# USB.net
KiCad netlist of a schematic drawn in Altium Designer
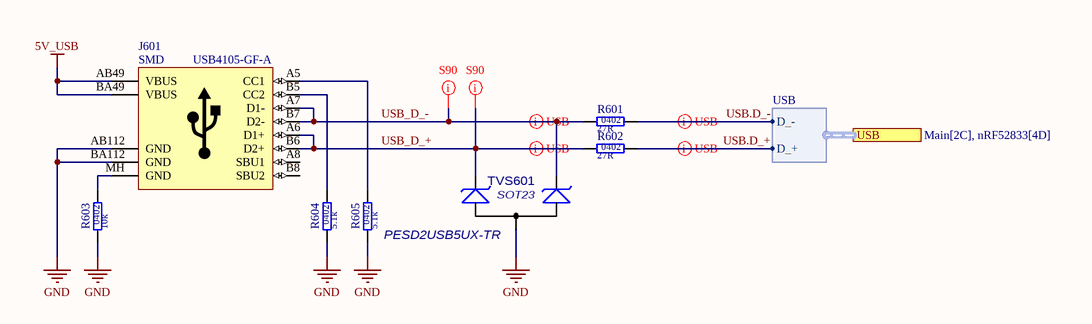
[diagram p0: USB.SchDoc]

(export (version "E")
  (design (tool "Eeschema 10.0.6"))
  (components
    (comp (ref "J601")
      (value "USB4105-GF-A")
      (footprint "J_USB_C_USB4105")
      (fields
        (field (name "SCH_FOOTPRINT") "SMD")
        (field (name "PART NUMBER") "J_USB_C_USB4105-GF-A")
        (field (name "MANUFACTURER") "GCT")
        (field (name "Comment") "USB C Connector")
      )
      (libsource (lib "Library") (part "J_USB_C_2.0_USB4105"))
    )
    (comp (ref "R601")
      (value "27R")
      (footprint "R_0402_1005")
      (fields
        (field (name "SCH_FOOTPRINT") "0402")
        (field (name "PART NUMBER") "R_27R_0402_1")
        (field (name "VOLTAGE") "50V")
        (field (name "POWER") "63mW")
      )
      (libsource (lib "Library") (part "R"))
    )
    (comp (ref "R602")
      (value "27R")
      (footprint "R_0402_1005")
      (fields
        (field (name "SCH_FOOTPRINT") "0402")
        (field (name "PART NUMBER") "R_27R_0402_1")
        (field (name "VOLTAGE") "50V")
        (field (name "POWER") "63mW")
      )
      (libsource (lib "Library") (part "R"))
    )
    (comp (ref "R603")
      (value "10k")
      (footprint "R_0402_1005")
      (fields
        (field (name "SCH_FOOTPRINT") "0402")
        (field (name "PART NUMBER") "R_10k_0402_1")
        (field (name "VOLTAGE") "50V")
        (field (name "POWER") "63mW")
      )
      (libsource (lib "Library") (part "R"))
    )
    (comp (ref "R604")
      (value "5.1k")
      (footprint "R_0402_1005")
      (fields
        (field (name "SCH_FOOTPRINT") "0402")
        (field (name "PART NUMBER") "R_5.1k_0402_1")
        (field (name "VOLTAGE") "50V")
        (field (name "POWER") "63mW")
      )
      (libsource (lib "Library") (part "R"))
    )
    (comp (ref "R605")
      (value "5.1k")
      (footprint "R_0402_1005")
      (fields
        (field (name "SCH_FOOTPRINT") "0402")
        (field (name "PART NUMBER") "R_5.1k_0402_1")
        (field (name "VOLTAGE") "50V")
        (field (name "POWER") "63mW")
      )
      (libsource (lib "Library") (part "R"))
    )
    (comp (ref "TVS601")
      (value "PESD2USB5UX-TR")
      (footprint "SOT23_N")
      (fields
        (field (name "SCH_FOOTPRINT") "SOT23")
        (field (name "PART NUMBER") "TVS_PESD2USB5UX-TR")
        (field (name "VOLTAGE") "5.0V")
        (field (name "MANUFACTURER") "Nexperia")
      )
      (libsource (lib "Library") (part "TVS_DOUBLE_SOT23-3"))
    )
  )
  (nets
    (net (code "2") (name "/USB.D_+") (class "Default")
      (node (ref "R602") (pin "2") (pinfunction "2_2") (pintype "passive"))
    )
    (net (code "3") (name "/USB.D_-") (class "Default")
      (node (ref "R601") (pin "2") (pinfunction "2_2") (pintype "passive"))
    )
    (net (code "4") (name "/USB_D_+") (class "Default")
      (node (ref "J601") (pin "A6") (pinfunction "D1+_A6") (pintype "bidirectional"))
      (node (ref "J601") (pin "B6") (pinfunction "D2+_B6") (pintype "bidirectional"))
      (node (ref "R602") (pin "1") (pinfunction "1_1") (pintype "passive"))
      (node (ref "TVS601") (pin "2") (pintype "passive"))
    )
    (net (code "5") (name "/USB_D_-") (class "Default")
      (node (ref "J601") (pin "A7") (pinfunction "D1-_A7") (pintype "bidirectional"))
      (node (ref "J601") (pin "B7") (pinfunction "D2-_B7") (pintype "bidirectional"))
      (node (ref "R601") (pin "1") (pinfunction "1_1") (pintype "passive"))
      (node (ref "TVS601") (pin "1") (pinfunction "100_1") (pintype "passive"))
    )
    (net (code "7") (name "5V_USB") (class "Default")
      (node (ref "J601") (pin "AB49") (pinfunction "VBUS_AB49") (pintype "power_in"))
      (node (ref "J601") (pin "BA49") (pinfunction "VBUS_BA49") (pintype "power_in"))
    )
    (net (code "8") (name "GND") (class "Default")
      (node (ref "J601") (pin "AB112") (pinfunction "GND_AB112") (pintype "power_in"))
      (node (ref "J601") (pin "BA112") (pinfunction "GND_BA112") (pintype "power_in"))
      (node (ref "R603") (pin "1") (pinfunction "1_1") (pintype "passive"))
      (node (ref "R604") (pin "1") (pinfunction "1_1") (pintype "passive"))
      (node (ref "R605") (pin "1") (pinfunction "1_1") (pintype "passive"))
      (node (ref "TVS601") (pin "3") (pintype "passive"))
    )
    (net (code "9") (name "Net-(J601-CC1)") (class "Default")
      (node (ref "J601") (pin "A5") (pinfunction "CC1_A5") (pintype "bidirectional"))
      (node (ref "R605") (pin "2") (pinfunction "2_2") (pintype "passive"))
    )
    (net (code "10") (name "Net-(J601-CC2)") (class "Default")
      (node (ref "J601") (pin "B5") (pinfunction "CC2_B5") (pintype "bidirectional"))
      (node (ref "R604") (pin "2") (pinfunction "2_2") (pintype "passive"))
    )
    (net (code "11") (name "Net-(J601-GND-PadMH)") (class "Default")
      (node (ref "J601") (pin "MH") (pinfunction "GND_MH") (pintype "power_in"))
      (node (ref "R603") (pin "2") (pinfunction "2_2") (pintype "passive"))
    )
    (net (code "12") (name "unconnected-(J601-SBU1-PadA8)") (class "Default")
      (node (ref "J601") (pin "A8") (pinfunction "SBU1_A8") (pintype "bidirectional"))
    )
    (net (code "13") (name "unconnected-(J601-SBU2-PadB8)") (class "Default")
      (node (ref "J601") (pin "B8") (pinfunction "SBU2_B8") (pintype "bidirectional"))
    )
  )
)
